# BatteryBoard.net
KiCad netlist of a schematic drawn in EAGLE
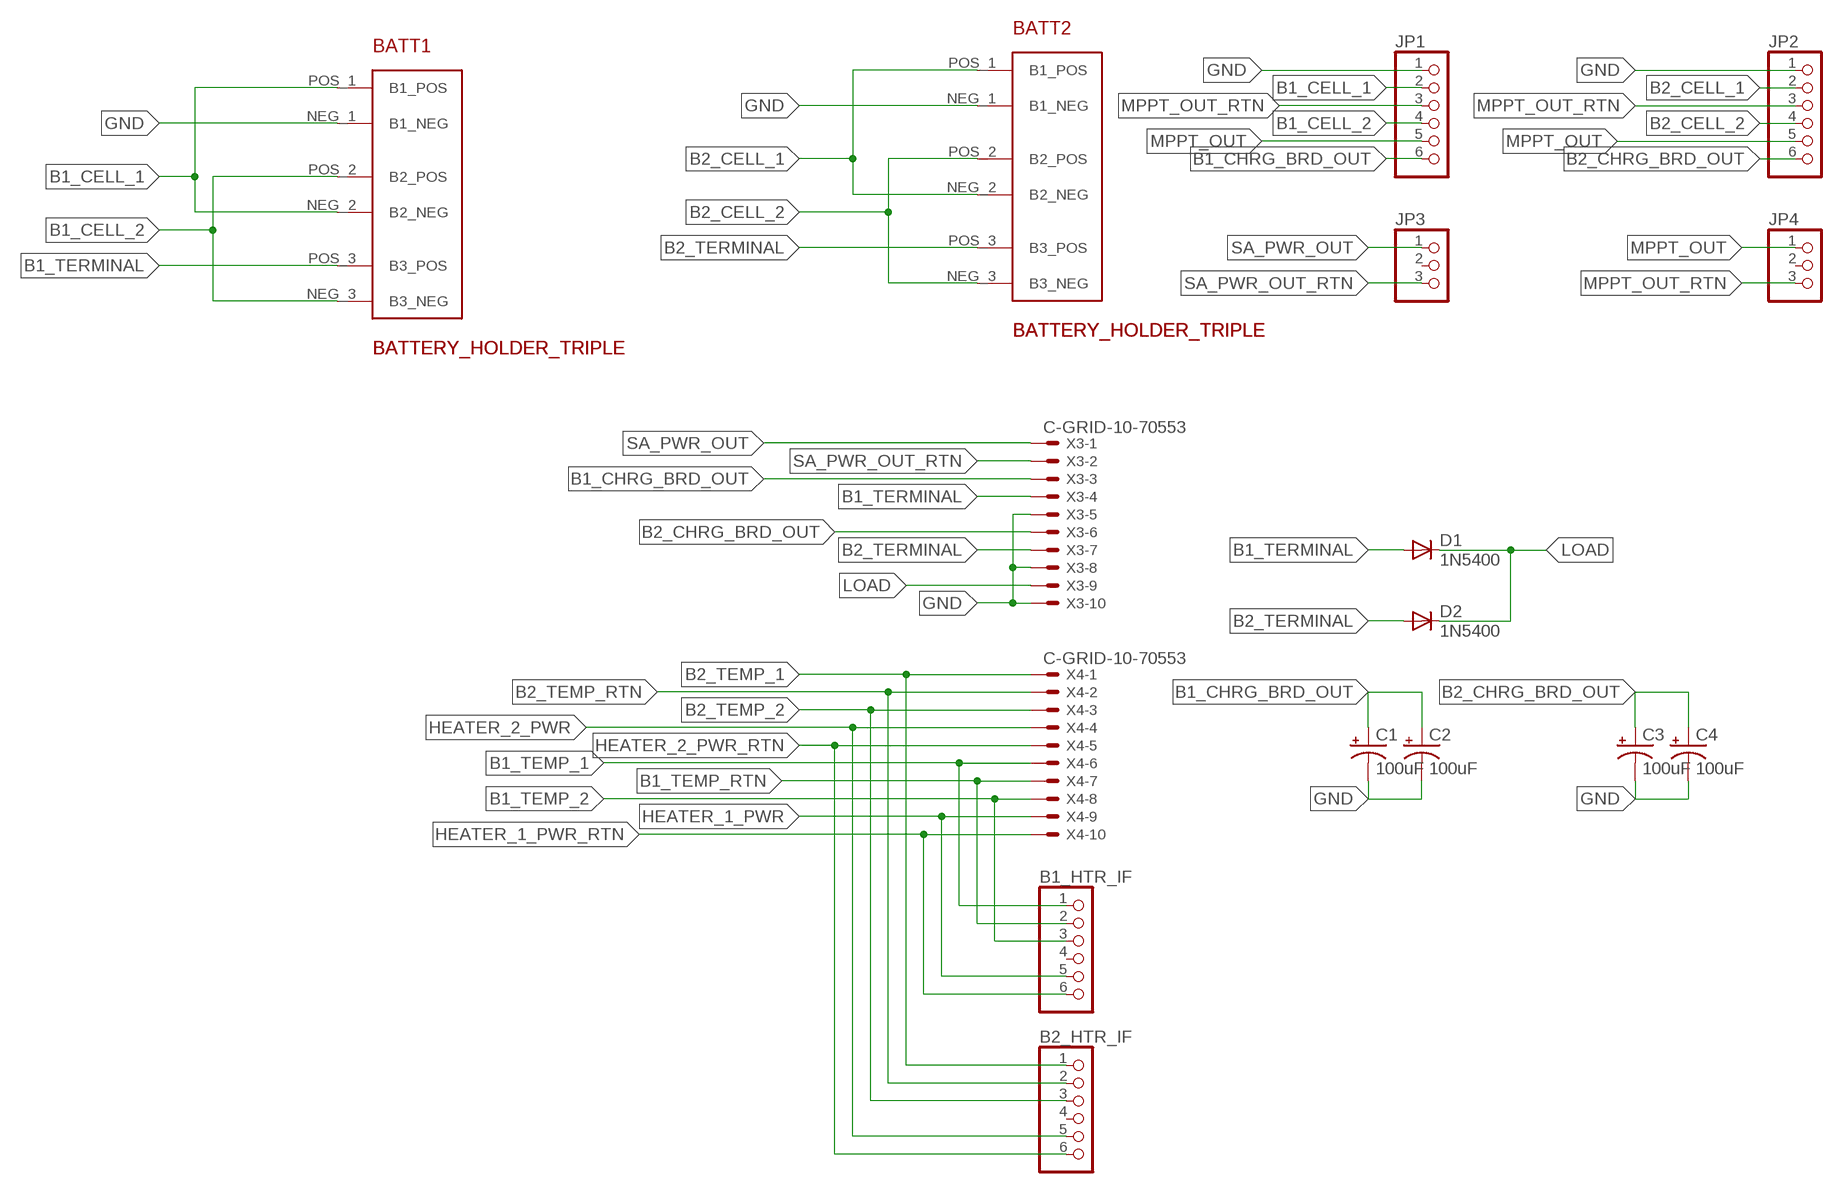
[diagram p0: schematic, sheet 1]

(export (version "E")
  (design (tool "Eeschema 10.0.6"))
  (components
    (comp (ref "B1_HTR_IF")
      (value "PINHD-1X6CLEAN")
      (footprint "eagle-import:1X06-CLEAN")
      (libsource (lib "eagle-import") (part "PINHD-1X6CLEAN"))
    )
    (comp (ref "B2_HTR_IF")
      (value "PINHD-1X6CLEAN")
      (footprint "eagle-import:1X06-CLEAN")
      (libsource (lib "eagle-import") (part "PINHD-1X6CLEAN"))
    )
    (comp (ref "BATT1")
      (value "BATTERY_HOLDER_TRIPLE")
      (footprint "eagle-import:BATT_HOLDER_SINGLE")
      (libsource (lib "eagle-import") (part "BATTERY_HOLDER_TRIPLE"))
    )
    (comp (ref "BATT2")
      (value "BATTERY_HOLDER_TRIPLE")
      (footprint "eagle-import:BATT_HOLDER_SINGLE")
      (libsource (lib "eagle-import") (part "BATTERY_HOLDER_TRIPLE"))
    )
    (comp (ref "C1")
      (value "100uF")
      (footprint "eagle-import:CT7343")
      (libsource (lib "eagle-import") (part "CPOL-USCT7343"))
    )
    (comp (ref "C2")
      (value "100uF")
      (footprint "eagle-import:CT7343")
      (libsource (lib "eagle-import") (part "CPOL-USCT7343"))
    )
    (comp (ref "C3")
      (value "100uF")
      (footprint "eagle-import:CT7343")
      (libsource (lib "eagle-import") (part "CPOL-USCT7343"))
    )
    (comp (ref "C4")
      (value "100uF")
      (footprint "eagle-import:CT7343")
      (libsource (lib "eagle-import") (part "CPOL-USCT7343"))
    )
    (comp (ref "D1")
      (value "1N5400")
      (footprint "eagle-import:DO201-15")
      (libsource (lib "eagle-import") (part "1N5400"))
    )
    (comp (ref "D2")
      (value "1N5400")
      (footprint "eagle-import:DO201-15")
      (libsource (lib "eagle-import") (part "1N5400"))
    )
    (comp (ref "JP1")
      (value "PINHD-1X6CLEAN")
      (footprint "eagle-import:1X06-CLEAN")
      (libsource (lib "eagle-import") (part "PINHD-1X6CLEAN"))
    )
    (comp (ref "JP2")
      (value "PINHD-1X6CLEAN")
      (footprint "eagle-import:1X06-CLEAN")
      (libsource (lib "eagle-import") (part "PINHD-1X6CLEAN"))
    )
    (comp (ref "JP3")
      (value "PINHD-1X3")
      (footprint "eagle-import:1X03")
      (libsource (lib "eagle-import") (part "PINHD-1X3"))
    )
    (comp (ref "JP4")
      (value "PINHD-1X3")
      (footprint "eagle-import:1X03")
      (libsource (lib "eagle-import") (part "PINHD-1X3"))
    )
    (comp (ref "X3")
      (value "C-GRID-10-70553")
      (footprint "eagle-import:70553-10")
      (libsource (lib "eagle-import") (part "C-GRID-10-70553"))
    )
    (comp (ref "X4")
      (value "C-GRID-10-70553")
      (footprint "eagle-import:70553-10")
      (libsource (lib "eagle-import") (part "C-GRID-10-70553"))
    )
  )
  (nets
    (net (code "1") (name "B1_CELL_1") (class "Default")
      (node (ref "BATT1") (pin "NEG_2") (pinfunction "B2_NEG_NEG_2") (pintype "bidirectional"))
      (node (ref "BATT1") (pin "POS_1") (pinfunction "B1_POS_POS_1") (pintype "bidirectional"))
      (node (ref "JP1") (pin "2") (pinfunction "2_2") (pintype "passive"))
    )
    (net (code "2") (name "B1_CELL_2") (class "Default")
      (node (ref "BATT1") (pin "NEG_3") (pinfunction "B3_NEG_NEG_3") (pintype "bidirectional"))
      (node (ref "BATT1") (pin "POS_2") (pinfunction "B2_POS_POS_2") (pintype "bidirectional"))
      (node (ref "JP1") (pin "4") (pinfunction "4_4") (pintype "passive"))
    )
    (net (code "3") (name "B1_CHRG_BRD_OUT") (class "Default")
      (node (ref "C1") (pin "+") (pinfunction "+_+") (pintype "passive"))
      (node (ref "C2") (pin "+") (pinfunction "+_+") (pintype "passive"))
      (node (ref "JP1") (pin "6") (pinfunction "6_6") (pintype "passive"))
      (node (ref "X3") (pin "3") (pinfunction "S_3") (pintype "passive"))
    )
    (net (code "4") (name "B1_TEMP_1") (class "Default")
      (node (ref "B1_HTR_IF") (pin "1") (pinfunction "1_1") (pintype "passive"))
      (node (ref "X4") (pin "6") (pinfunction "S_6") (pintype "passive"))
    )
    (net (code "5") (name "B1_TEMP_2") (class "Default")
      (node (ref "B1_HTR_IF") (pin "3") (pinfunction "3_3") (pintype "passive"))
      (node (ref "X4") (pin "8") (pinfunction "S_8") (pintype "passive"))
    )
    (net (code "6") (name "B1_TEMP_RTN") (class "Default")
      (node (ref "B1_HTR_IF") (pin "2") (pinfunction "2_2") (pintype "passive"))
      (node (ref "X4") (pin "7") (pinfunction "S_7") (pintype "passive"))
    )
    (net (code "7") (name "B1_TERMINAL") (class "Default")
      (node (ref "BATT1") (pin "POS_3") (pinfunction "B3_POS_POS_3") (pintype "bidirectional"))
      (node (ref "D1") (pin "A") (pinfunction "A_A") (pintype "passive"))
      (node (ref "X3") (pin "4") (pinfunction "S_4") (pintype "passive"))
    )
    (net (code "8") (name "B2_CELL_1") (class "Default")
      (node (ref "BATT2") (pin "NEG_2") (pinfunction "B2_NEG_NEG_2") (pintype "bidirectional"))
      (node (ref "BATT2") (pin "POS_1") (pinfunction "B1_POS_POS_1") (pintype "bidirectional"))
      (node (ref "JP2") (pin "2") (pinfunction "2_2") (pintype "passive"))
    )
    (net (code "9") (name "B2_CELL_2") (class "Default")
      (node (ref "BATT2") (pin "NEG_3") (pinfunction "B3_NEG_NEG_3") (pintype "bidirectional"))
      (node (ref "BATT2") (pin "POS_2") (pinfunction "B2_POS_POS_2") (pintype "bidirectional"))
      (node (ref "JP2") (pin "4") (pinfunction "4_4") (pintype "passive"))
    )
    (net (code "10") (name "B2_CHRG_BRD_OUT") (class "Default")
      (node (ref "C3") (pin "+") (pinfunction "+_+") (pintype "passive"))
      (node (ref "C4") (pin "+") (pinfunction "+_+") (pintype "passive"))
      (node (ref "JP2") (pin "6") (pinfunction "6_6") (pintype "passive"))
      (node (ref "X3") (pin "6") (pinfunction "S_6") (pintype "passive"))
    )
    (net (code "11") (name "B2_TEMP_1") (class "Default")
      (node (ref "B2_HTR_IF") (pin "1") (pinfunction "1_1") (pintype "passive"))
      (node (ref "X4") (pin "1") (pinfunction "S_1") (pintype "passive"))
    )
    (net (code "12") (name "B2_TEMP_2") (class "Default")
      (node (ref "B2_HTR_IF") (pin "3") (pinfunction "3_3") (pintype "passive"))
      (node (ref "X4") (pin "3") (pinfunction "S_3") (pintype "passive"))
    )
    (net (code "13") (name "B2_TEMP_RTN") (class "Default")
      (node (ref "B2_HTR_IF") (pin "2") (pinfunction "2_2") (pintype "passive"))
      (node (ref "X4") (pin "2") (pinfunction "S_2") (pintype "passive"))
    )
    (net (code "14") (name "B2_TERMINAL") (class "Default")
      (node (ref "BATT2") (pin "POS_3") (pinfunction "B3_POS_POS_3") (pintype "bidirectional"))
      (node (ref "D2") (pin "A") (pinfunction "A_A") (pintype "passive"))
      (node (ref "X3") (pin "7") (pinfunction "S_7") (pintype "passive"))
    )
    (net (code "15") (name "GND") (class "Default")
      (node (ref "BATT1") (pin "NEG_1") (pinfunction "B1_NEG_NEG_1") (pintype "bidirectional"))
      (node (ref "BATT2") (pin "NEG_1") (pinfunction "B1_NEG_NEG_1") (pintype "bidirectional"))
      (node (ref "C1") (pin "-") (pinfunction "-_-") (pintype "passive"))
      (node (ref "C2") (pin "-") (pinfunction "-_-") (pintype "passive"))
      (node (ref "C3") (pin "-") (pinfunction "-_-") (pintype "passive"))
      (node (ref "C4") (pin "-") (pinfunction "-_-") (pintype "passive"))
      (node (ref "JP1") (pin "1") (pinfunction "1_1") (pintype "passive"))
      (node (ref "JP2") (pin "1") (pinfunction "1_1") (pintype "passive"))
      (node (ref "X3") (pin "10") (pinfunction "S_10") (pintype "passive"))
      (node (ref "X3") (pin "5") (pinfunction "S_5") (pintype "passive"))
      (node (ref "X3") (pin "8") (pinfunction "S_8") (pintype "passive"))
    )
    (net (code "16") (name "HEATER_1_PWR") (class "Default")
      (node (ref "B1_HTR_IF") (pin "5") (pinfunction "5_5") (pintype "passive"))
      (node (ref "X4") (pin "9") (pinfunction "S_9") (pintype "passive"))
    )
    (net (code "17") (name "HEATER_1_PWR_RTN") (class "Default")
      (node (ref "B1_HTR_IF") (pin "6") (pinfunction "6_6") (pintype "passive"))
      (node (ref "X4") (pin "10") (pinfunction "S_10") (pintype "passive"))
    )
    (net (code "18") (name "HEATER_2_PWR") (class "Default")
      (node (ref "B2_HTR_IF") (pin "5") (pinfunction "5_5") (pintype "passive"))
      (node (ref "X4") (pin "4") (pinfunction "S_4") (pintype "passive"))
    )
    (net (code "19") (name "HEATER_2_PWR_RTN") (class "Default")
      (node (ref "B2_HTR_IF") (pin "6") (pinfunction "6_6") (pintype "passive"))
      (node (ref "X4") (pin "5") (pinfunction "S_5") (pintype "passive"))
    )
    (net (code "20") (name "LOAD") (class "Default")
      (node (ref "D1") (pin "C") (pinfunction "C_C") (pintype "passive"))
      (node (ref "D2") (pin "C") (pinfunction "C_C") (pintype "passive"))
      (node (ref "X3") (pin "9") (pinfunction "S_9") (pintype "passive"))
    )
    (net (code "21") (name "MPPT_OUT") (class "Default")
      (node (ref "JP1") (pin "5") (pinfunction "5_5") (pintype "passive"))
      (node (ref "JP2") (pin "5") (pinfunction "5_5") (pintype "passive"))
      (node (ref "JP4") (pin "1") (pinfunction "1_1") (pintype "passive"))
    )
    (net (code "22") (name "MPPT_OUT_RTN") (class "Default")
      (node (ref "JP1") (pin "3") (pinfunction "3_3") (pintype "passive"))
      (node (ref "JP2") (pin "3") (pinfunction "3_3") (pintype "passive"))
      (node (ref "JP4") (pin "3") (pinfunction "3_3") (pintype "passive"))
    )
    (net (code "23") (name "SA_PWR_OUT") (class "Default")
      (node (ref "JP3") (pin "1") (pinfunction "1_1") (pintype "passive"))
      (node (ref "X3") (pin "1") (pinfunction "S_1") (pintype "passive"))
    )
    (net (code "24") (name "SA_PWR_OUT_RTN") (class "Default")
      (node (ref "JP3") (pin "3") (pinfunction "3_3") (pintype "passive"))
      (node (ref "X3") (pin "2") (pinfunction "S_2") (pintype "passive"))
    )
    (net (code "25") (name "unconnected-(B1_HTR_IF-Pad4)") (class "Default")
      (node (ref "B1_HTR_IF") (pin "4") (pinfunction "4_4") (pintype "passive"))
    )
    (net (code "26") (name "unconnected-(B2_HTR_IF-Pad4)") (class "Default")
      (node (ref "B2_HTR_IF") (pin "4") (pinfunction "4_4") (pintype "passive"))
    )
    (net (code "27") (name "unconnected-(JP3-Pad2)") (class "Default")
      (node (ref "JP3") (pin "2") (pinfunction "2_2") (pintype "passive"))
    )
    (net (code "28") (name "unconnected-(JP4-Pad2)") (class "Default")
      (node (ref "JP4") (pin "2") (pinfunction "2_2") (pintype "passive"))
    )
  )
)
